# reset.net
KiCad netlist of a schematic drawn in Altium Designer
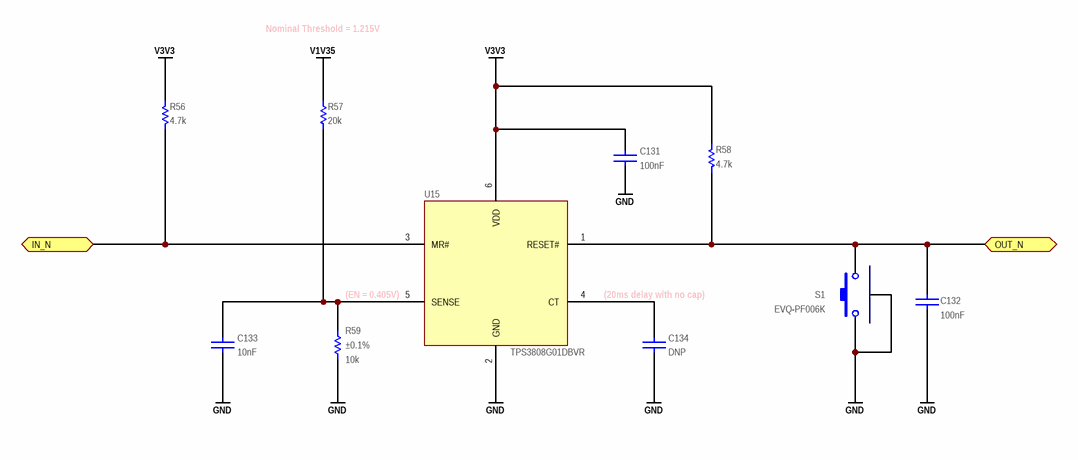
[diagram p0: reset.SchDoc]

(export (version "E")
  (design (tool "Eeschema 10.0.6"))
  (components
    (comp (ref "C131")
      (value "100nF")
      (footprint "CAPC100X50X55L25N")
      (description "Ceramic Capacitor 100nF ±10% 50V X7R 0402")
      (fields (field (name "MANUFACTURER") "Murata") (field (name "TOLERANCE") "±10%"))
      (libsource (lib "") (part "CAP_1"))
    )
    (comp (ref "C132")
      (value "100nF")
      (footprint "CAPC100X50X55L25N")
      (description "Ceramic Capacitor 100nF ±10% 50V X7R 0402")
      (fields (field (name "MANUFACTURER") "Murata") (field (name "TOLERANCE") "±10%"))
      (libsource (lib "generic") (part "CAP"))
    )
    (comp (ref "C133")
      (value "10nF")
      (footprint "CAPC100X50X55L25N")
      (description "Ceramic Capacitor 10nF ±10% 50V X7R 0402")
      (fields (field (name "MANUFACTURER") "Murata") (field (name "TOLERANCE") "±10%"))
      (libsource (lib "") (part "CAP_1"))
    )
    (comp (ref "C134")
      (value "CAP 0805")
      (footprint "CAPC200X125X145L45N")
      (description "Capacitor 0805")
      (fields (field (name "DO NOT PLACE") "DNP"))
      (libsource (lib "") (part "CAP_1"))
    )
    (comp (ref "R56")
      (value "4.7k")
      (footprint "RESC1005X40N")
      (description "Thick Film Resistor 4.7k ±1% 0.1W 75V 0402")
      (fields (field (name "TOLERANCE") "±1%") (field (name "MANUFACTURER") "Panasonic"))
      (libsource (lib "generic") (part "RES"))
    )
    (comp (ref "R57")
      (value "20k")
      (footprint "RESC2012X70N")
      (description "Thin Film Resistor 20k ±0.1% 0.125W 100V 0805")
      (fields (field (name "TOLERANCE") "±0.1%") (field (name "MANUFACTURER") "Panasonic"))
      (libsource (lib "generic") (part "RES"))
    )
    (comp (ref "R58")
      (value "4.7k")
      (footprint "RESC1005X40N")
      (description "Thick Film Resistor 4.7k ±1% 0.1W 75V 0402")
      (fields (field (name "TOLERANCE") "±1%") (field (name "MANUFACTURER") "Panasonic"))
      (libsource (lib "generic") (part "RES"))
    )
    (comp (ref "R59")
      (value "10k")
      (footprint "RESC2012X70N")
      (description "Thin Film Resistor 10k ±0.1% 0.125W 100V 0805")
      (fields
        (field (name "TOLERANCE") "±0.1%")
        (field (name "MANUFACTURER") "Panasonic")
        (field (name "VOLTAGE") "100")
      )
      (libsource (lib "generic") (part "RES"))
    )
    (comp (ref "S1")
      (value "EVQ-PF006K")
      (footprint "EVQ-PF006K")
      (description "Tactile Switch; Normally Open")
      (fields (field (name "MANUFACTURER") "Panasonic"))
      (libsource (lib "panasonic") (part "EVQ-PF006K"))
    )
    (comp (ref "U15")
      (value "TPS3808G01DBVR")
      (footprint "DBV-6")
      (description "Low Quiescent Current, Programmable-Delay  Supervisory Circuit")
      (fields (field (name "MANUFACTURER") "Texas Instruments"))
      (libsource (lib "shit") (part "TPS3808"))
    )
  )
  (nets
    (net (code "1") (name "/IN_N") (class "Default")
      (node (ref "R56") (pin "1") (pinfunction "1_1") (pintype "passive"))
      (node (ref "U15") (pin "3") (pinfunction "MR#_3") (pintype "passive"))
    )
    (net (code "2") (name "/OUT_N") (class "Default")
      (node (ref "C132") (pin "2") (pinfunction "2_2") (pintype "passive"))
      (node (ref "R58") (pin "1") (pinfunction "1_1") (pintype "passive"))
      (node (ref "S1") (pin "2") (pinfunction "2_2") (pintype "passive"))
      (node (ref "U15") (pin "1") (pinfunction "RESET#_1") (pintype "passive"))
    )
    (net (code "3") (name "GND") (class "Default")
      (node (ref "C131") (pin "2") (pinfunction "2_2") (pintype "passive"))
      (node (ref "C132") (pin "1") (pinfunction "1_1") (pintype "passive"))
      (node (ref "C133") (pin "2") (pinfunction "2_2") (pintype "passive"))
      (node (ref "C134") (pin "2") (pinfunction "2_2") (pintype "passive"))
      (node (ref "R59") (pin "1") (pinfunction "1_1") (pintype "passive"))
      (node (ref "S1") (pin "1") (pinfunction "1_1") (pintype "passive"))
      (node (ref "S1") (pin "3") (pinfunction "3_3") (pintype "passive"))
      (node (ref "U15") (pin "2") (pinfunction "GND_2") (pintype "passive"))
    )
    (net (code "4") (name "Net-(U15-CT)") (class "Default")
      (node (ref "C134") (pin "1") (pinfunction "1_1") (pintype "passive"))
      (node (ref "U15") (pin "4") (pinfunction "CT_4") (pintype "passive"))
    )
    (net (code "5") (name "Net-(U15-SENSE)") (class "Default")
      (node (ref "C133") (pin "1") (pinfunction "1_1") (pintype "passive"))
      (node (ref "R57") (pin "1") (pinfunction "1_1") (pintype "passive"))
      (node (ref "R59") (pin "2") (pinfunction "2_2") (pintype "passive"))
      (node (ref "U15") (pin "5") (pinfunction "SENSE_5") (pintype "passive"))
    )
    (net (code "6") (name "V1V35") (class "Default")
      (node (ref "R57") (pin "2") (pinfunction "2_2") (pintype "passive"))
    )
    (net (code "7") (name "V3V3") (class "Default")
      (node (ref "C131") (pin "1") (pinfunction "1_1") (pintype "passive"))
      (node (ref "R56") (pin "2") (pinfunction "2_2") (pintype "passive"))
      (node (ref "R58") (pin "2") (pinfunction "2_2") (pintype "passive"))
      (node (ref "U15") (pin "6") (pinfunction "VDD_6") (pintype "passive"))
    )
  )
)
